# pc-register.net
KiCad netlist of a schematic drawn in EAGLE
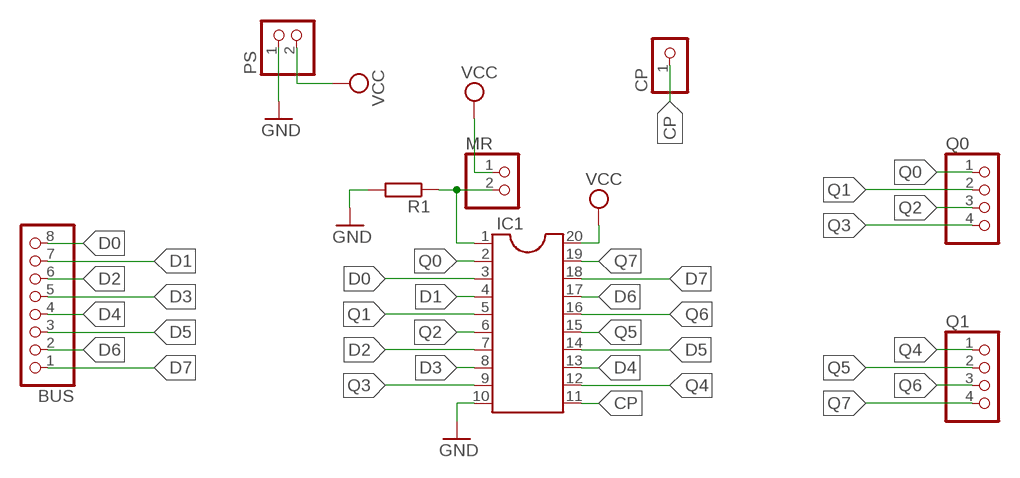
[diagram p0: schematic, sheet 1]

(export (version "E")
  (design (tool "Eeschema 10.0.6"))
  (components
    (comp (ref "BUS")
      (value "PINHD-1X8")
      (footprint "eagle-import:1X08")
      (libsource (lib "eagle-import") (part "PINHD-1X8"))
    )
    (comp (ref "CP")
      (value "PINHD-1X1")
      (footprint "eagle-import:1X01")
      (libsource (lib "eagle-import") (part "PINHD-1X1"))
    )
    (comp (ref "IC1")
      (value "DIL20S")
      (footprint "eagle-import:SOCKET-20")
      (libsource (lib "eagle-import") (part "DIL20S"))
    )
    (comp (ref "MR")
      (value "PINHD-1X2")
      (footprint "eagle-import:1X02")
      (libsource (lib "eagle-import") (part "PINHD-1X2"))
    )
    (comp (ref "PS")
      (value "PINHD-1X2")
      (footprint "eagle-import:1X02")
      (libsource (lib "eagle-import") (part "PINHD-1X2"))
    )
    (comp (ref "Q0")
      (value "PINHD-1X4")
      (footprint "eagle-import:1X04")
      (libsource (lib "eagle-import") (part "PINHD-1X4"))
    )
    (comp (ref "Q1")
      (value "PINHD-1X4")
      (footprint "eagle-import:1X04")
      (libsource (lib "eagle-import") (part "PINHD-1X4"))
    )
    (comp (ref "R1")
      (value "R-EU_0204/7")
      (footprint "eagle-import:0204_7")
      (libsource (lib "eagle-import") (part "R-EU_0204/7"))
    )
  )
  (nets
    (net (code "1") (name "CP") (class "Default")
      (node (ref "CP") (pin "1") (pinfunction "1_1") (pintype "passive"))
      (node (ref "IC1") (pin "11") (pinfunction "11_11") (pintype "passive"))
    )
    (net (code "2") (name "D0") (class "Default")
      (node (ref "BUS") (pin "8") (pinfunction "8_8") (pintype "passive"))
      (node (ref "IC1") (pin "3") (pinfunction "3_3") (pintype "passive"))
    )
    (net (code "3") (name "D1") (class "Default")
      (node (ref "BUS") (pin "7") (pinfunction "7_7") (pintype "passive"))
      (node (ref "IC1") (pin "4") (pinfunction "4_4") (pintype "passive"))
    )
    (net (code "4") (name "D2") (class "Default")
      (node (ref "BUS") (pin "6") (pinfunction "6_6") (pintype "passive"))
      (node (ref "IC1") (pin "7") (pinfunction "7_7") (pintype "passive"))
    )
    (net (code "5") (name "D3") (class "Default")
      (node (ref "BUS") (pin "5") (pinfunction "5_5") (pintype "passive"))
      (node (ref "IC1") (pin "8") (pinfunction "8_8") (pintype "passive"))
    )
    (net (code "6") (name "D4") (class "Default")
      (node (ref "BUS") (pin "4") (pinfunction "4_4") (pintype "passive"))
      (node (ref "IC1") (pin "13") (pinfunction "13_13") (pintype "passive"))
    )
    (net (code "7") (name "D5") (class "Default")
      (node (ref "BUS") (pin "3") (pinfunction "3_3") (pintype "passive"))
      (node (ref "IC1") (pin "14") (pinfunction "14_14") (pintype "passive"))
    )
    (net (code "8") (name "D6") (class "Default")
      (node (ref "BUS") (pin "2") (pinfunction "2_2") (pintype "passive"))
      (node (ref "IC1") (pin "17") (pinfunction "17_17") (pintype "passive"))
    )
    (net (code "9") (name "D7") (class "Default")
      (node (ref "BUS") (pin "1") (pinfunction "1_1") (pintype "passive"))
      (node (ref "IC1") (pin "18") (pinfunction "18_18") (pintype "passive"))
    )
    (net (code "10") (name "GND") (class "Default")
      (node (ref "IC1") (pin "10") (pinfunction "10_10") (pintype "passive"))
      (node (ref "PS") (pin "1") (pinfunction "1_1") (pintype "passive"))
      (node (ref "R1") (pin "2") (pinfunction "2_2") (pintype "passive"))
    )
    (net (code "11") (name "Net-(IC1-Pad1)") (class "Default")
      (node (ref "IC1") (pin "1") (pinfunction "1_1") (pintype "passive"))
      (node (ref "MR") (pin "2") (pinfunction "2_2") (pintype "passive"))
      (node (ref "R1") (pin "1") (pinfunction "1_1") (pintype "passive"))
    )
    (net (code "12") (name "Q0") (class "Default")
      (node (ref "IC1") (pin "2") (pinfunction "2_2") (pintype "passive"))
      (node (ref "Q0") (pin "1") (pinfunction "1_1") (pintype "passive"))
    )
    (net (code "13") (name "Q1") (class "Default")
      (node (ref "IC1") (pin "5") (pinfunction "5_5") (pintype "passive"))
      (node (ref "Q0") (pin "2") (pinfunction "2_2") (pintype "passive"))
    )
    (net (code "14") (name "Q2") (class "Default")
      (node (ref "IC1") (pin "6") (pinfunction "6_6") (pintype "passive"))
      (node (ref "Q0") (pin "3") (pinfunction "3_3") (pintype "passive"))
    )
    (net (code "15") (name "Q3") (class "Default")
      (node (ref "IC1") (pin "9") (pinfunction "9_9") (pintype "passive"))
      (node (ref "Q0") (pin "4") (pinfunction "4_4") (pintype "passive"))
    )
    (net (code "16") (name "Q4") (class "Default")
      (node (ref "IC1") (pin "12") (pinfunction "12_12") (pintype "passive"))
      (node (ref "Q1") (pin "1") (pinfunction "1_1") (pintype "passive"))
    )
    (net (code "17") (name "Q5") (class "Default")
      (node (ref "IC1") (pin "15") (pinfunction "15_15") (pintype "passive"))
      (node (ref "Q1") (pin "2") (pinfunction "2_2") (pintype "passive"))
    )
    (net (code "18") (name "Q6") (class "Default")
      (node (ref "IC1") (pin "16") (pinfunction "16_16") (pintype "passive"))
      (node (ref "Q1") (pin "3") (pinfunction "3_3") (pintype "passive"))
    )
    (net (code "19") (name "Q7") (class "Default")
      (node (ref "IC1") (pin "19") (pinfunction "19_19") (pintype "passive"))
      (node (ref "Q1") (pin "4") (pinfunction "4_4") (pintype "passive"))
    )
    (net (code "20") (name "VCC") (class "Default")
      (node (ref "IC1") (pin "20") (pinfunction "20_20") (pintype "passive"))
      (node (ref "MR") (pin "1") (pinfunction "1_1") (pintype "passive"))
      (node (ref "PS") (pin "2") (pinfunction "2_2") (pintype "passive"))
    )
  )
)
